# Orin_Hat.net
KiCad netlist of a schematic drawn in Altium Designer
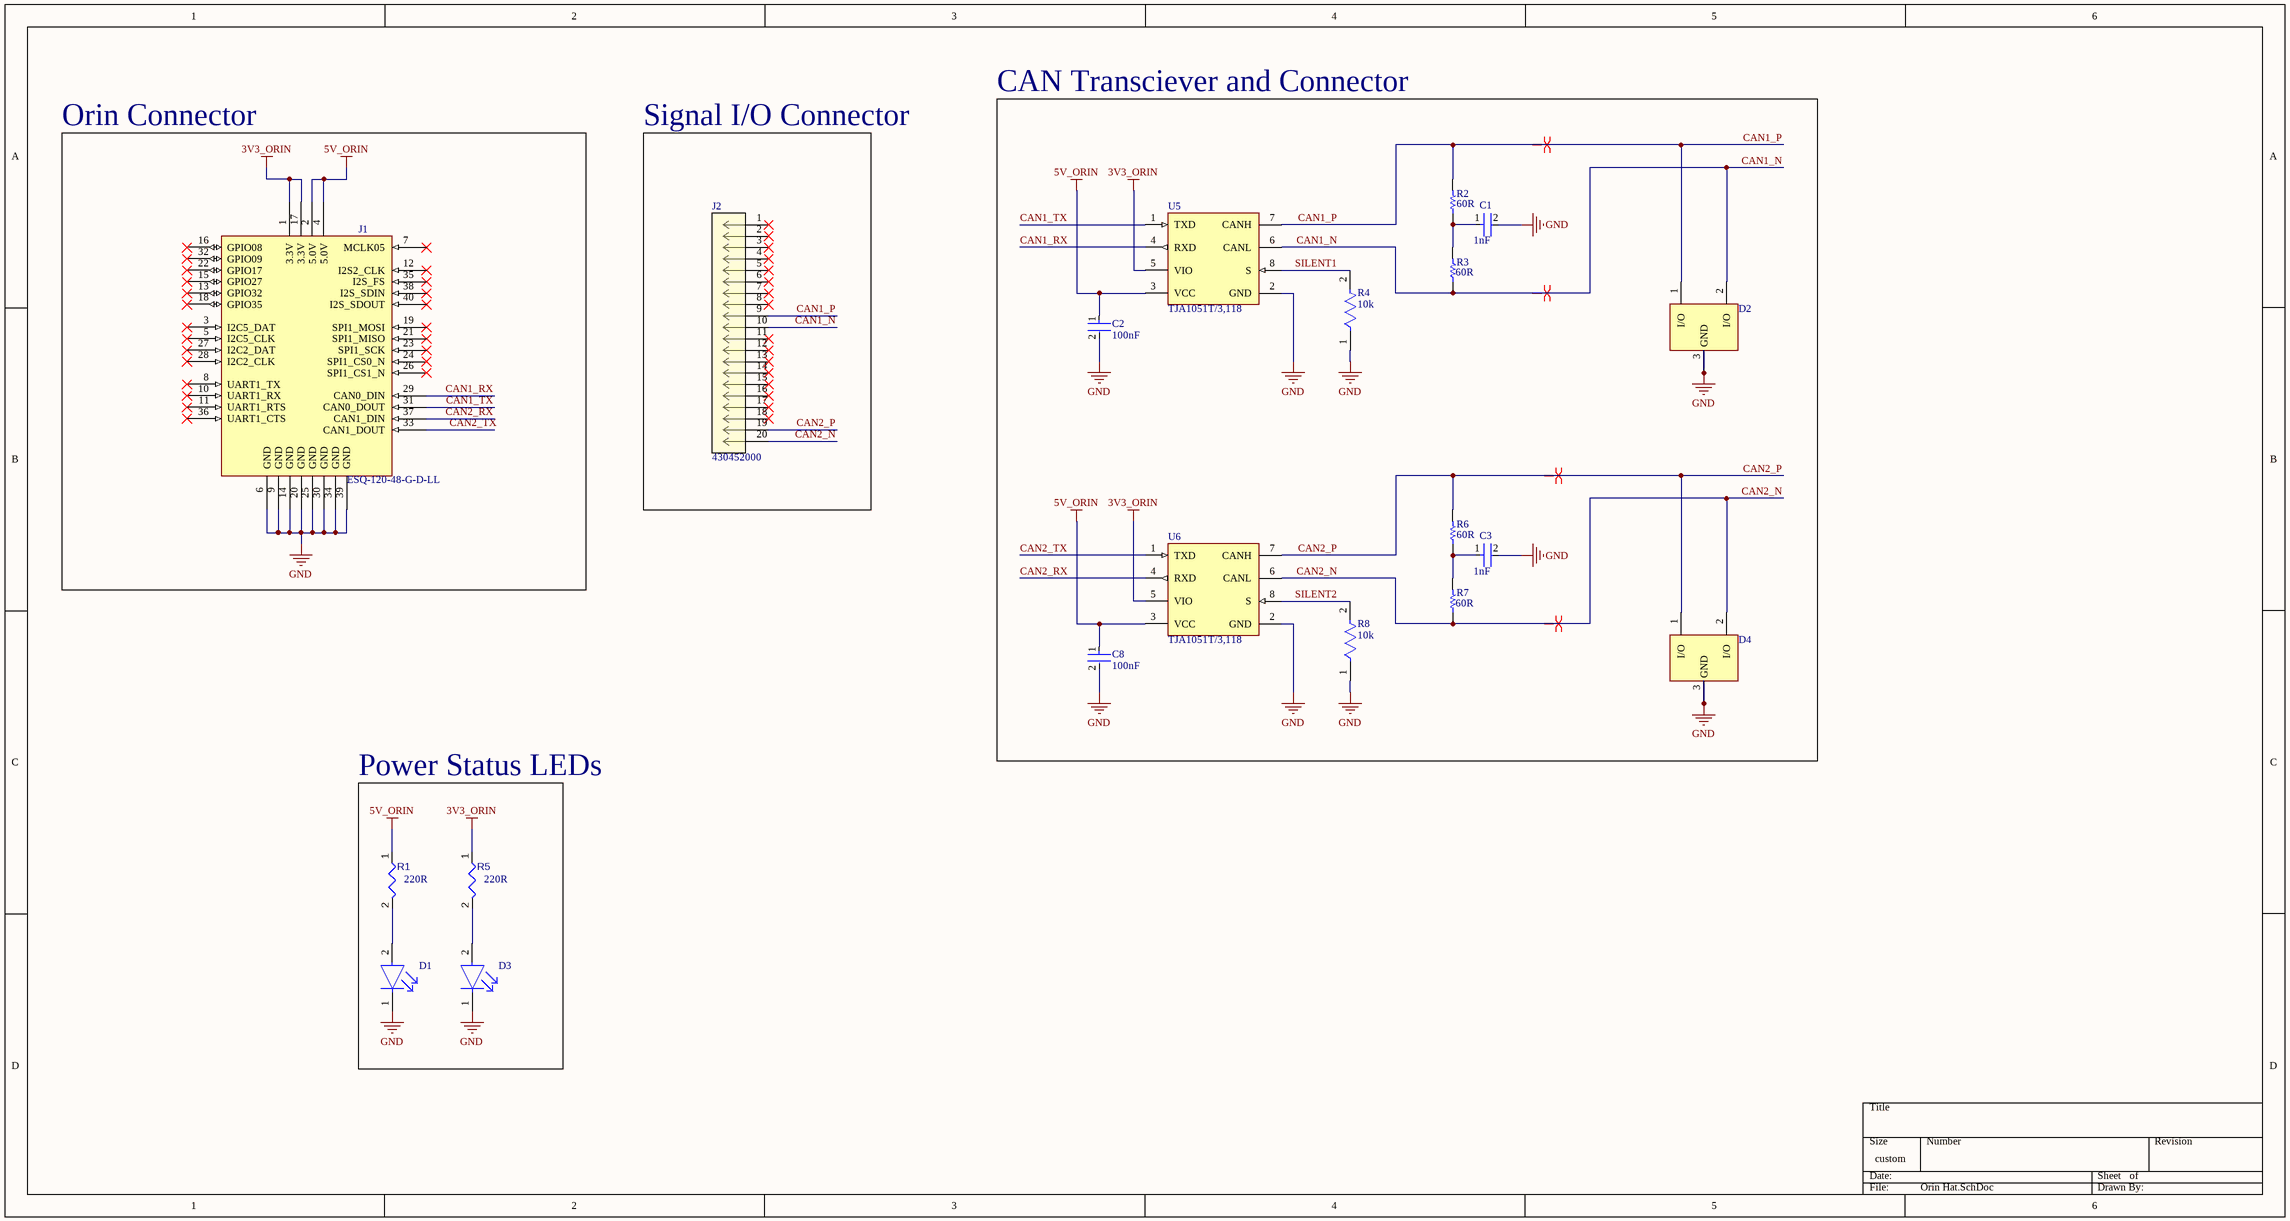
[diagram p0: Orin Hat.SchDoc]

(export (version "E")
  (design (tool "Eeschema 10.0.6"))
  (components
    (comp (ref "C1")
      (value "1nF")
      (footprint "FP-C0805C-DN-MFG")
      (description "CAP CER 1000PF 50V X7R 0805")
      (fields
        (field (name "OCTOPART") "https://octopart.com/c0805c102k5ractu-kemet-93010")
        (field (name "TOLERANCE") "0.1")
      )
      (libsource (lib "Altium Content Vault") (part "b4654b650e69147ec39a6b967a45e02"))
    )
    (comp (ref "C2")
      (value "100nF")
      (footprint "FP-C0603C-CF-IPC_B")
      (description "CAP CER 0.1UF 50V X7R 0603")
      (fields
        (field (name "MANUFACTURER") "KEMET")
        (field (name "OCTOPART") "https://octopart.com/c0603c104k5racauto-kemet-12563741")
      )
      (libsource (lib "Altium Content Vault") (part "b4654b650e69147ec39a6b967a45e02"))
    )
    (comp (ref "C3")
      (value "1nF")
      (footprint "FP-C0805C-DN-MFG")
      (description "CAP CER 1000PF 50V X7R 0805")
      (fields
        (field (name "OCTOPART") "https://octopart.com/c0805c102k5ractu-kemet-93010")
        (field (name "TOLERANCE") "0.1")
      )
      (libsource (lib "Altium Content Vault") (part "b4654b650e69147ec39a6b967a45e02"))
    )
    (comp (ref "C8")
      (value "100nF")
      (footprint "FP-C0603C-CF-IPC_B")
      (description "CAP CER 0.1UF 50V X7R 0603")
      (fields
        (field (name "MANUFACTURER") "KEMET")
        (field (name "OCTOPART") "https://octopart.com/c0603c104k5racauto-kemet-12563741")
      )
      (libsource (lib "Altium Content Vault") (part "b4654b650e69147ec39a6b967a45e02"))
    )
    (comp (ref "D1")
      (value "APT1608ZGCK")
      (footprint "FP-APT1608ZGCK-MFG")
      (description "LED GREEN CLEAR CHIP SMD")
      (libsource (lib "Altium Content Vault") (part "8706943c75ba83719d021d2fdc84c58"))
    )
    (comp (ref "D2")
      (value "ESD2CAN24DCKRQ1")
      (footprint "SOT65P210X110-3N")
      (libsource (lib "Tyler's Workspace") (part "ESD2CAN24DCKRQ1-Symbol-1"))
    )
    (comp (ref "D3")
      (value "APT1608ZGCK")
      (footprint "FP-APT1608ZGCK-MFG")
      (description "LED GREEN CLEAR CHIP SMD")
      (libsource (lib "Altium Content Vault") (part "8706943c75ba83719d021d2fdc84c58"))
    )
    (comp (ref "D4")
      (value "ESD2CAN24DCKRQ1")
      (footprint "SOT65P210X110-3N")
      (libsource (lib "Tyler's Workspace") (part "ESD2CAN24DCKRQ1-Symbol-1"))
    )
    (comp (ref "J1")
      (value "ESQ-120-48-G-D-LL")
      (footprint "ESQ-120-48-G-D-LL-Footprint-1")
      (libsource (lib "Tyler's Workspace") (part "ESQ-120-48-G-D-LL-Symbol-1"))
    )
    (comp (ref "J2")
      (value "430452000")
      (footprint "CON_430452000_MOL")
      (description "No Description Available")
      (libsource (lib "430452000") (part "430452000"))
    )
    (comp (ref "R1")
      (value "220R")
      (footprint "RESC2012X06N")
      (description "General Purpose Chip Resistor Thick Film 0805 220Ohm 5% Paper T/R")
      (fields (field (name "Comment") "RC0805JR-7W220RL"))
      (libsource (lib "Tyler's Workspace") (part "RES-2"))
    )
    (comp (ref "R2")
      (value "60R")
      (footprint "RESC2013X60X35ML10T20")
      (fields (field (name "PART NUMBER") "RC0805FR-0760R4L") (field (name "MANUFACTURER") "Yageo"))
      (libsource (lib "Altium Content Vault") (part "RES"))
    )
    (comp (ref "R3")
      (value "60R")
      (footprint "RESC2013X60X35ML10T20")
      (fields (field (name "PART NUMBER") "RC0805FR-0760R4L") (field (name "MANUFACTURER") "Yageo"))
      (libsource (lib "Altium Content Vault") (part "RES"))
    )
    (comp (ref "R4")
      (value "RC0603FR-0710KL")
      (footprint "FP-RC0603-0_55-IPC_B")
      (description "RES 10K OHM 1% 1/10W 0603")
      (fields (field (name "TOLERANCE") "1%") (field (name "RESISTANCE") "10k"))
      (libsource (lib "Altium Content Vault") (part "1029c3af85768c4190bb7ad29bc67b5"))
    )
    (comp (ref "R5")
      (value "220R")
      (footprint "RESC2012X06N")
      (description "General Purpose Chip Resistor Thick Film 0805 220Ohm 5% Paper T/R")
      (fields (field (name "Comment") "RC0805JR-7W220RL"))
      (libsource (lib "Tyler's Workspace") (part "RES-2"))
    )
    (comp (ref "R6")
      (value "60R")
      (footprint "RESC2013X60X35ML10T20")
      (fields (field (name "PART NUMBER") "RC0805FR-0760R4L") (field (name "MANUFACTURER") "Yageo"))
      (libsource (lib "Altium Content Vault") (part "RES"))
    )
    (comp (ref "R7")
      (value "60R")
      (footprint "RESC2013X60X35ML10T20")
      (fields (field (name "PART NUMBER") "RC0805FR-0760R4L") (field (name "MANUFACTURER") "Yageo"))
      (libsource (lib "Altium Content Vault") (part "RES"))
    )
    (comp (ref "R8")
      (value "RC0603FR-0710KL")
      (footprint "FP-RC0603-0_55-IPC_B")
      (description "RES 10K OHM 1% 1/10W 0603")
      (fields (field (name "TOLERANCE") "1%") (field (name "RESISTANCE") "10k"))
      (libsource (lib "Altium Content Vault") (part "1029c3af85768c4190bb7ad29bc67b5"))
    )
    (comp (ref "U5")
      (value "TJA1051T/3,118")
      (footprint "NXP-SOIC-8_L")
      (description "High-Speed CAN Transceiver, 3 to 5 V, 8-Pin SOIC (SOT96-1), RoHS, Tape and Reel")
      (fields (field (name "MANUFACTURER") "NXP"))
      (libsource (lib "Altium Content Vault") (part "NXP-TJA1051T_3-SOIC-8"))
    )
    (comp (ref "U6")
      (value "TJA1051T/3,118")
      (footprint "NXP-SOIC-8_L")
      (description "High-Speed CAN Transceiver, 3 to 5 V, 8-Pin SOIC (SOT96-1), RoHS, Tape and Reel")
      (fields (field (name "MANUFACTURER") "NXP"))
      (libsource (lib "Altium Content Vault") (part "NXP-TJA1051T_3-SOIC-8"))
    )
  )
  (nets
    (net (code "1") (name "/CAN1_N") (class "Default")
      (node (ref "D2") (pin "2") (pinfunction "I/O_2") (pintype "passive"))
      (node (ref "J2") (pin "10") (pinfunction "10_10") (pintype "passive"))
      (node (ref "R3") (pin "1") (pinfunction "1_1") (pintype "passive"))
      (node (ref "U5") (pin "6") (pinfunction "CANL_6") (pintype "passive"))
    )
    (net (code "2") (name "/CAN1_P") (class "Default")
      (node (ref "D2") (pin "1") (pinfunction "I/O_1") (pintype "passive"))
      (node (ref "J2") (pin "9") (pinfunction "9_9") (pintype "passive"))
      (node (ref "R2") (pin "2") (pinfunction "2_2") (pintype "passive"))
      (node (ref "U5") (pin "7") (pinfunction "CANH_7") (pintype "passive"))
    )
    (net (code "3") (name "/CAN1_RX") (class "Default")
      (node (ref "J1") (pin "29") (pinfunction "CAN0_DIN_29") (pintype "input"))
      (node (ref "U5") (pin "4") (pinfunction "RXD_4") (pintype "output"))
    )
    (net (code "4") (name "/CAN1_TX") (class "Default")
      (node (ref "J1") (pin "31") (pinfunction "CAN0_DOUT_31") (pintype "input"))
      (node (ref "U5") (pin "1") (pinfunction "TXD_1") (pintype "input"))
    )
    (net (code "5") (name "/CAN2_N") (class "Default")
      (node (ref "D4") (pin "2") (pinfunction "I/O_2") (pintype "passive"))
      (node (ref "J2") (pin "20") (pinfunction "20_20") (pintype "passive"))
      (node (ref "R7") (pin "1") (pinfunction "1_1") (pintype "passive"))
      (node (ref "U6") (pin "6") (pinfunction "CANL_6") (pintype "passive"))
    )
    (net (code "6") (name "/CAN2_P") (class "Default")
      (node (ref "D4") (pin "1") (pinfunction "I/O_1") (pintype "passive"))
      (node (ref "J2") (pin "19") (pinfunction "19_19") (pintype "passive"))
      (node (ref "R6") (pin "2") (pinfunction "2_2") (pintype "passive"))
      (node (ref "U6") (pin "7") (pinfunction "CANH_7") (pintype "passive"))
    )
    (net (code "7") (name "/CAN2_RX") (class "Default")
      (node (ref "J1") (pin "37") (pinfunction "CAN1_DIN_37") (pintype "input"))
      (node (ref "U6") (pin "4") (pinfunction "RXD_4") (pintype "output"))
    )
    (net (code "8") (name "/CAN2_TX") (class "Default")
      (node (ref "J1") (pin "33") (pinfunction "CAN1_DOUT_33") (pintype "input"))
      (node (ref "U6") (pin "1") (pinfunction "TXD_1") (pintype "input"))
    )
    (net (code "9") (name "/SILENT1") (class "Default")
      (node (ref "R4") (pin "2") (pinfunction "2_2") (pintype "passive"))
      (node (ref "U5") (pin "8") (pinfunction "S_8") (pintype "input"))
    )
    (net (code "10") (name "/SILENT2") (class "Default")
      (node (ref "R8") (pin "2") (pinfunction "2_2") (pintype "passive"))
      (node (ref "U6") (pin "8") (pinfunction "S_8") (pintype "input"))
    )
    (net (code "11") (name "3V3_ORIN") (class "Default")
      (node (ref "J1") (pin "1") (pinfunction "3.3V_1") (pintype "power_in"))
      (node (ref "J1") (pin "17") (pinfunction "3.3V_17") (pintype "power_in"))
      (node (ref "R5") (pin "1") (pinfunction "1_1") (pintype "passive"))
      (node (ref "U5") (pin "5") (pinfunction "VIO_5") (pintype "power_in"))
      (node (ref "U6") (pin "5") (pinfunction "VIO_5") (pintype "power_in"))
    )
    (net (code "12") (name "5V_ORIN") (class "Default")
      (node (ref "C2") (pin "1") (pinfunction "1_1") (pintype "passive"))
      (node (ref "C8") (pin "1") (pinfunction "1_1") (pintype "passive"))
      (node (ref "J1") (pin "2") (pinfunction "5.0V_2") (pintype "power_in"))
      (node (ref "J1") (pin "4") (pinfunction "5.0V_4") (pintype "power_in"))
      (node (ref "R1") (pin "1") (pinfunction "1_1") (pintype "passive"))
      (node (ref "U5") (pin "3") (pinfunction "VCC_3") (pintype "power_in"))
      (node (ref "U6") (pin "3") (pinfunction "VCC_3") (pintype "power_in"))
    )
    (net (code "13") (name "GND") (class "Default")
      (node (ref "C1") (pin "2") (pinfunction "2_2") (pintype "passive"))
      (node (ref "C2") (pin "2") (pinfunction "2_2") (pintype "passive"))
      (node (ref "C3") (pin "2") (pinfunction "2_2") (pintype "passive"))
      (node (ref "C8") (pin "2") (pinfunction "2_2") (pintype "passive"))
      (node (ref "D1") (pin "1") (pinfunction "C_1") (pintype "passive"))
      (node (ref "D2") (pin "3") (pinfunction "GND_3") (pintype "passive"))
      (node (ref "D3") (pin "1") (pinfunction "C_1") (pintype "passive"))
      (node (ref "D4") (pin "3") (pinfunction "GND_3") (pintype "passive"))
      (node (ref "J1") (pin "14") (pinfunction "GND_14") (pintype "power_in"))
      (node (ref "J1") (pin "20") (pinfunction "GND_20") (pintype "power_in"))
      (node (ref "J1") (pin "25") (pinfunction "GND_25") (pintype "power_in"))
      (node (ref "J1") (pin "30") (pinfunction "GND_30") (pintype "power_in"))
      (node (ref "J1") (pin "34") (pinfunction "GND_34") (pintype "power_in"))
      (node (ref "J1") (pin "39") (pinfunction "GND_39") (pintype "power_in"))
      (node (ref "J1") (pin "6") (pinfunction "GND_6") (pintype "power_in"))
      (node (ref "J1") (pin "9") (pinfunction "GND_9") (pintype "power_in"))
      (node (ref "R4") (pin "1") (pinfunction "1_1") (pintype "passive"))
      (node (ref "R8") (pin "1") (pinfunction "1_1") (pintype "passive"))
      (node (ref "U5") (pin "2") (pinfunction "GND_2") (pintype "power_in"))
      (node (ref "U6") (pin "2") (pinfunction "GND_2") (pintype "power_in"))
    )
    (net (code "14") (name "Net-(C1-Pad1)") (class "Default")
      (node (ref "C1") (pin "1") (pinfunction "1_1") (pintype "passive"))
      (node (ref "R2") (pin "1") (pinfunction "1_1") (pintype "passive"))
      (node (ref "R3") (pin "2") (pinfunction "2_2") (pintype "passive"))
    )
    (net (code "15") (name "Net-(C3-Pad1)") (class "Default")
      (node (ref "C3") (pin "1") (pinfunction "1_1") (pintype "passive"))
      (node (ref "R6") (pin "1") (pinfunction "1_1") (pintype "passive"))
      (node (ref "R7") (pin "2") (pinfunction "2_2") (pintype "passive"))
    )
    (net (code "16") (name "Net-(D1-A)") (class "Default")
      (node (ref "D1") (pin "2") (pinfunction "A_2") (pintype "passive"))
      (node (ref "R1") (pin "2") (pinfunction "2_2") (pintype "passive"))
    )
    (net (code "17") (name "Net-(D3-A)") (class "Default")
      (node (ref "D3") (pin "2") (pinfunction "A_2") (pintype "passive"))
      (node (ref "R5") (pin "2") (pinfunction "2_2") (pintype "passive"))
    )
    (net (code "18") (name "unconnected-(J1-GPIO08-Pad16)") (class "Default")
      (node (ref "J1") (pin "16") (pinfunction "GPIO08_16") (pintype "bidirectional+no_connect"))
    )
    (net (code "19") (name "unconnected-(J1-GPIO09-Pad32)") (class "Default")
      (node (ref "J1") (pin "32") (pinfunction "GPIO09_32") (pintype "bidirectional+no_connect"))
    )
    (net (code "20") (name "unconnected-(J1-GPIO17-Pad22)") (class "Default")
      (node (ref "J1") (pin "22") (pinfunction "GPIO17_22") (pintype "bidirectional+no_connect"))
    )
    (net (code "21") (name "unconnected-(J1-GPIO27-Pad15)") (class "Default")
      (node (ref "J1") (pin "15") (pinfunction "GPIO27_15") (pintype "bidirectional+no_connect"))
    )
    (net (code "22") (name "unconnected-(J1-GPIO32-Pad13)") (class "Default")
      (node (ref "J1") (pin "13") (pinfunction "GPIO32_13") (pintype "bidirectional+no_connect"))
    )
    (net (code "23") (name "unconnected-(J1-GPIO35-Pad18)") (class "Default")
      (node (ref "J1") (pin "18") (pinfunction "GPIO35_18") (pintype "bidirectional+no_connect"))
    )
    (net (code "24") (name "unconnected-(J1-I2C2_CLK-Pad28)") (class "Default")
      (node (ref "J1") (pin "28") (pinfunction "I2C2_CLK_28") (pintype "input+no_connect"))
    )
    (net (code "25") (name "unconnected-(J1-I2C2_DAT-Pad27)") (class "Default")
      (node (ref "J1") (pin "27") (pinfunction "I2C2_DAT_27") (pintype "input+no_connect"))
    )
    (net (code "26") (name "unconnected-(J1-I2C5_CLK-Pad5)") (class "Default")
      (node (ref "J1") (pin "5") (pinfunction "I2C5_CLK_5") (pintype "input+no_connect"))
    )
    (net (code "27") (name "unconnected-(J1-I2C5_DAT-Pad3)") (class "Default")
      (node (ref "J1") (pin "3") (pinfunction "I2C5_DAT_3") (pintype "input+no_connect"))
    )
    (net (code "28") (name "unconnected-(J1-I2S2_CLK-Pad12)") (class "Default")
      (node (ref "J1") (pin "12") (pinfunction "I2S2_CLK_12") (pintype "input+no_connect"))
    )
    (net (code "29") (name "unconnected-(J1-I2S_FS-Pad35)") (class "Default")
      (node (ref "J1") (pin "35") (pinfunction "I2S_FS_35") (pintype "input+no_connect"))
    )
    (net (code "30") (name "unconnected-(J1-I2S_SDIN-Pad38)") (class "Default")
      (node (ref "J1") (pin "38") (pinfunction "I2S_SDIN_38") (pintype "input+no_connect"))
    )
    (net (code "31") (name "unconnected-(J1-I2S_SDOUT-Pad40)") (class "Default")
      (node (ref "J1") (pin "40") (pinfunction "I2S_SDOUT_40") (pintype "input+no_connect"))
    )
    (net (code "32") (name "unconnected-(J1-MCLK05-Pad7)") (class "Default")
      (node (ref "J1") (pin "7") (pinfunction "MCLK05_7") (pintype "input+no_connect"))
    )
    (net (code "33") (name "unconnected-(J1-SPI1_CS0_N-Pad24)") (class "Default")
      (node (ref "J1") (pin "24") (pinfunction "SPI1_CS0_N_24") (pintype "input+no_connect"))
    )
    (net (code "34") (name "unconnected-(J1-SPI1_CS1_N-Pad26)") (class "Default")
      (node (ref "J1") (pin "26") (pinfunction "SPI1_CS1_N_26") (pintype "input+no_connect"))
    )
    (net (code "35") (name "unconnected-(J1-SPI1_MISO-Pad21)") (class "Default")
      (node (ref "J1") (pin "21") (pinfunction "SPI1_MISO_21") (pintype "input+no_connect"))
    )
    (net (code "36") (name "unconnected-(J1-SPI1_MOSI-Pad19)") (class "Default")
      (node (ref "J1") (pin "19") (pinfunction "SPI1_MOSI_19") (pintype "input+no_connect"))
    )
    (net (code "37") (name "unconnected-(J1-SPI1_SCK-Pad23)") (class "Default")
      (node (ref "J1") (pin "23") (pinfunction "SPI1_SCK_23") (pintype "input+no_connect"))
    )
    (net (code "38") (name "unconnected-(J1-UART1_CTS-Pad36)") (class "Default")
      (node (ref "J1") (pin "36") (pinfunction "UART1_CTS_36") (pintype "input+no_connect"))
    )
    (net (code "39") (name "unconnected-(J1-UART1_RTS-Pad11)") (class "Default")
      (node (ref "J1") (pin "11") (pinfunction "UART1_RTS_11") (pintype "input+no_connect"))
    )
    (net (code "40") (name "unconnected-(J1-UART1_RX-Pad10)") (class "Default")
      (node (ref "J1") (pin "10") (pinfunction "UART1_RX_10") (pintype "input+no_connect"))
    )
    (net (code "41") (name "unconnected-(J1-UART1_TX-Pad8)") (class "Default")
      (node (ref "J1") (pin "8") (pinfunction "UART1_TX_8") (pintype "input+no_connect"))
    )
    (net (code "42") (name "unconnected-(J2-Pad1)") (class "Default")
      (node (ref "J2") (pin "1") (pinfunction "1_1") (pintype "passive+no_connect"))
    )
    (net (code "43") (name "unconnected-(J2-Pad2)") (class "Default")
      (node (ref "J2") (pin "2") (pinfunction "2_2") (pintype "passive+no_connect"))
    )
    (net (code "44") (name "unconnected-(J2-Pad3)") (class "Default")
      (node (ref "J2") (pin "3") (pinfunction "3_3") (pintype "passive+no_connect"))
    )
    (net (code "45") (name "unconnected-(J2-Pad4)") (class "Default")
      (node (ref "J2") (pin "4") (pinfunction "4_4") (pintype "passive+no_connect"))
    )
    (net (code "46") (name "unconnected-(J2-Pad5)") (class "Default")
      (node (ref "J2") (pin "5") (pinfunction "5_5") (pintype "passive+no_connect"))
    )
    (net (code "47") (name "unconnected-(J2-Pad6)") (class "Default")
      (node (ref "J2") (pin "6") (pinfunction "6_6") (pintype "passive+no_connect"))
    )
    (net (code "48") (name "unconnected-(J2-Pad7)") (class "Default")
      (node (ref "J2") (pin "7") (pinfunction "7_7") (pintype "passive+no_connect"))
    )
    (net (code "49") (name "unconnected-(J2-Pad8)") (class "Default")
      (node (ref "J2") (pin "8") (pinfunction "8_8") (pintype "passive+no_connect"))
    )
    (net (code "50") (name "unconnected-(J2-Pad11)") (class "Default")
      (node (ref "J2") (pin "11") (pinfunction "11_11") (pintype "passive+no_connect"))
    )
    (net (code "51") (name "unconnected-(J2-Pad12)") (class "Default")
      (node (ref "J2") (pin "12") (pinfunction "12_12") (pintype "passive+no_connect"))
    )
    (net (code "52") (name "unconnected-(J2-Pad13)") (class "Default")
      (node (ref "J2") (pin "13") (pinfunction "13_13") (pintype "passive+no_connect"))
    )
    (net (code "53") (name "unconnected-(J2-Pad14)") (class "Default")
      (node (ref "J2") (pin "14") (pinfunction "14_14") (pintype "passive+no_connect"))
    )
    (net (code "54") (name "unconnected-(J2-Pad15)") (class "Default")
      (node (ref "J2") (pin "15") (pinfunction "15_15") (pintype "passive+no_connect"))
    )
    (net (code "55") (name "unconnected-(J2-Pad16)") (class "Default")
      (node (ref "J2") (pin "16") (pinfunction "16_16") (pintype "passive+no_connect"))
    )
    (net (code "56") (name "unconnected-(J2-Pad17)") (class "Default")
      (node (ref "J2") (pin "17") (pinfunction "17_17") (pintype "passive+no_connect"))
    )
    (net (code "57") (name "unconnected-(J2-Pad18)") (class "Default")
      (node (ref "J2") (pin "18") (pinfunction "18_18") (pintype "passive+no_connect"))
    )
  )
)
